# sapflux_base_v2_1.net
KiCad netlist of a schematic drawn in EAGLE
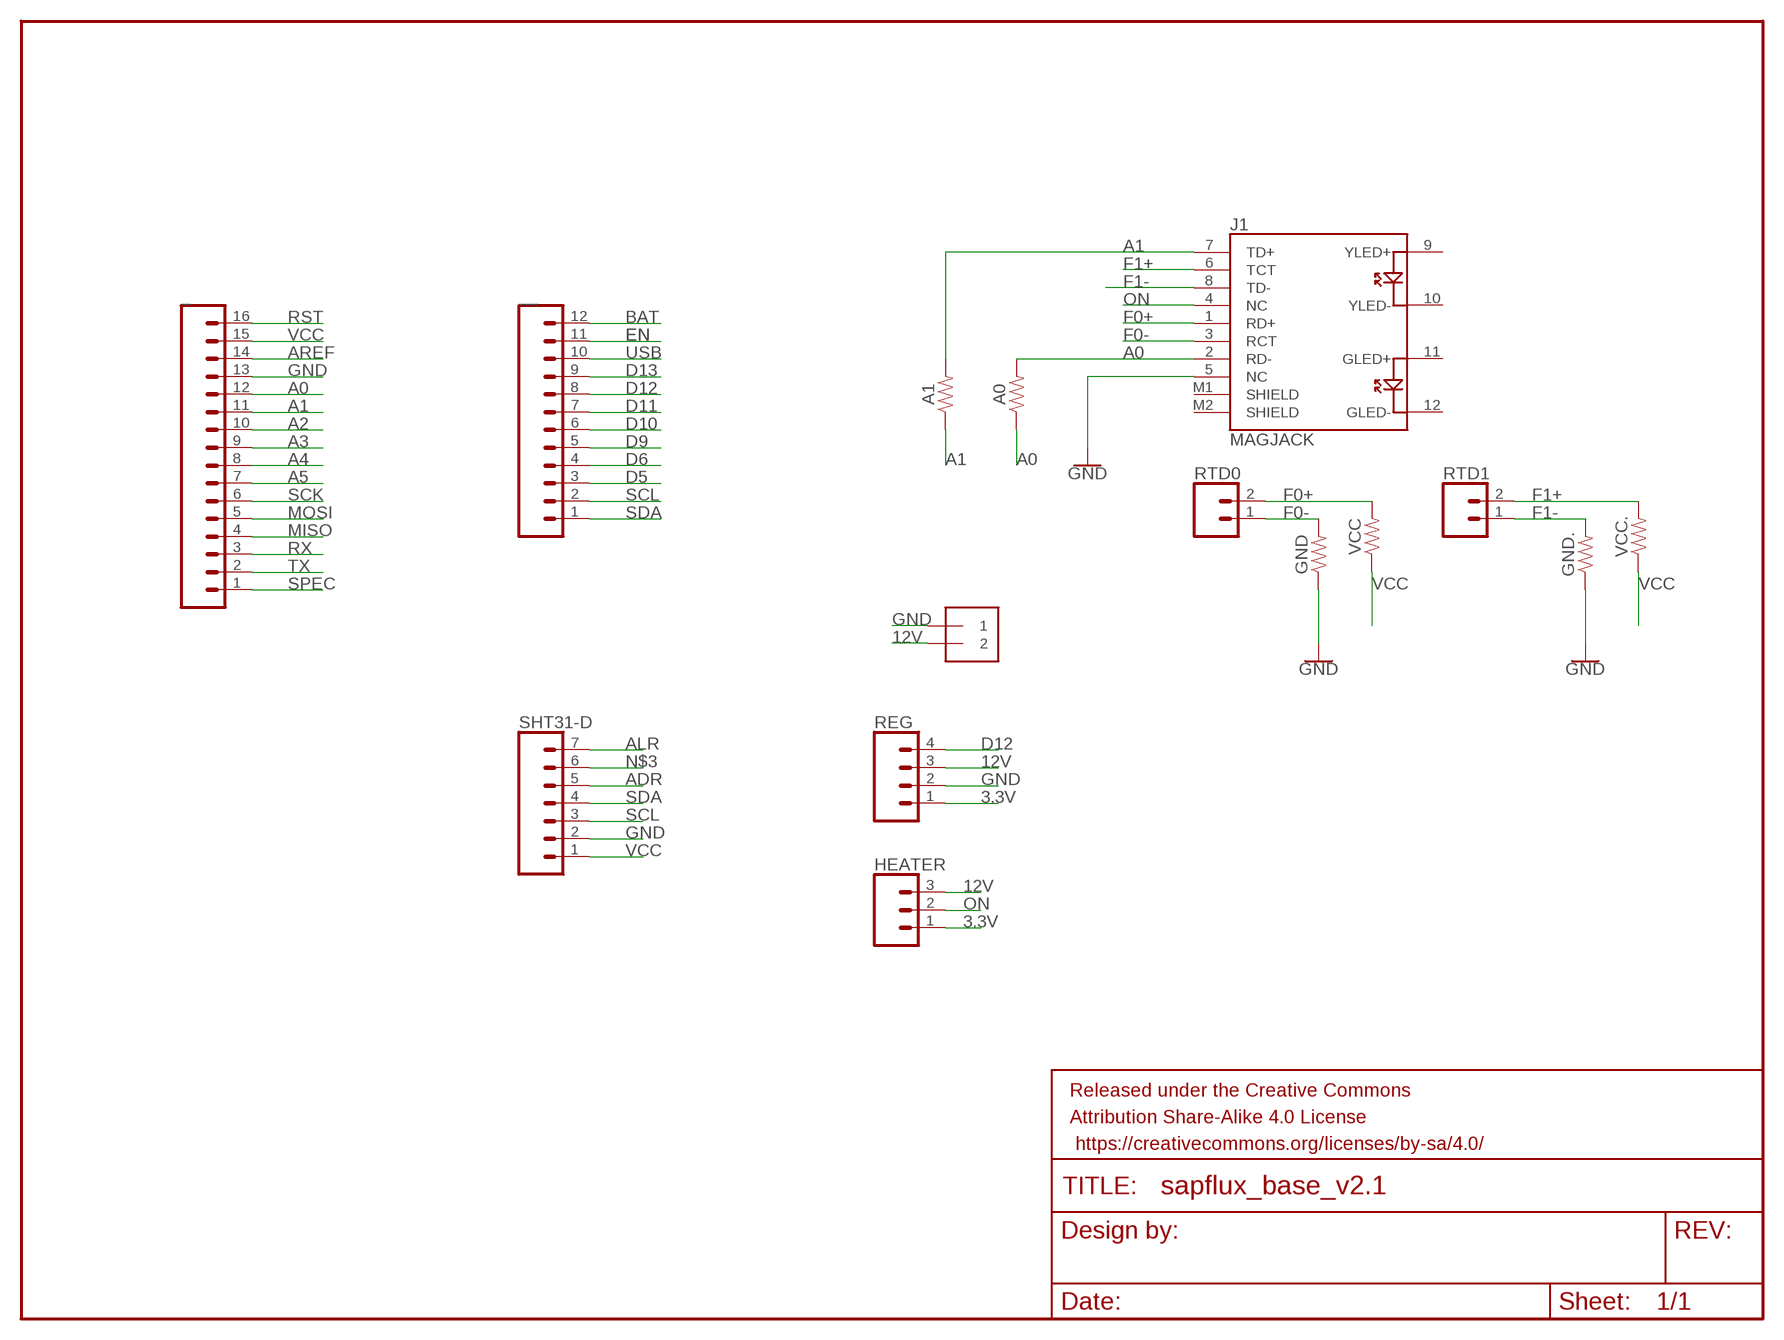
[diagram p0: schematic, sheet 1]

(export (version "E")
  (design (tool "Eeschema 10.0.6"))
  (components
    (comp (ref ".")
      (value "1X2-3.5MM")
      (footprint "eagle-import:1X2-3.5MM")
      (libsource (lib "eagle-import") (part "1X2-3.5MM"))
    )
    (comp (ref "A0")
      (value "1.8MOHM")
      (footprint "eagle-import:0603")
      (libsource (lib "eagle-import") (part "1.8MOHM"))
    )
    (comp (ref "A1")
      (value "1.8MOHM")
      (footprint "eagle-import:0603")
      (libsource (lib "eagle-import") (part "1.8MOHM"))
    )
    (comp (ref "FRAME1")
      (value "FRAME-LETTER")
      (footprint "eagle-import:CREATIVE_COMMONS")
      (libsource (lib "eagle-import") (part "FRAME-LETTER"))
    )
    (comp (ref "GND")
      (value "1.8MOHM")
      (footprint "eagle-import:0603")
      (libsource (lib "eagle-import") (part "1.8MOHM"))
    )
    (comp (ref "GND.")
      (value "1.8MOHM")
      (footprint "eagle-import:0603")
      (libsource (lib "eagle-import") (part "1.8MOHM"))
    )
    (comp (ref "HEATER")
      (value "CONN_03")
      (footprint "eagle-import:1X03")
      (libsource (lib "eagle-import") (part "CONN_03"))
    )
    (comp (ref "J1")
      (value "MAGJACK")
      (footprint "eagle-import:MAGJACK")
      (libsource (lib "eagle-import") (part "MAGJACK"))
    )
    (comp (ref "REG")
      (value "CONN_04")
      (footprint "eagle-import:1X04")
      (libsource (lib "eagle-import") (part "CONN_04"))
    )
    (comp (ref "RTD0")
      (value "CONN_02")
      (footprint "eagle-import:1X02")
      (libsource (lib "eagle-import") (part "CONN_02"))
    )
    (comp (ref "RTD1")
      (value "CONN_02")
      (footprint "eagle-import:1X02")
      (libsource (lib "eagle-import") (part "CONN_02"))
    )
    (comp (ref "SHT31-D")
      (value "CONN_07")
      (footprint "eagle-import:1X07")
      (libsource (lib "eagle-import") (part "CONN_07"))
    )
    (comp (ref "VCC")
      (value "1.8MOHM")
      (footprint "eagle-import:0603")
      (libsource (lib "eagle-import") (part "1.8MOHM"))
    )
    (comp (ref "VCC.")
      (value "1.8MOHM")
      (footprint "eagle-import:0603")
      (libsource (lib "eagle-import") (part "1.8MOHM"))
    )
    (comp (ref "_")
      (value "CONN_16")
      (footprint "eagle-import:1X16")
      (libsource (lib "eagle-import") (part "CONN_16"))
    )
    (comp (ref "__")
      (value "CONN_12")
      (footprint "eagle-import:1X12")
      (libsource (lib "eagle-import") (part "CONN_12"))
    )
  )
  (nets
    (net (code "1") (name "/3.3V") (class "Default")
      (node (ref "HEATER") (pin "1") (pinfunction "1_1") (pintype "passive"))
      (node (ref "REG") (pin "1") (pinfunction "1_1") (pintype "passive"))
    )
    (net (code "2") (name "/12V") (class "Default")
      (node (ref ".") (pin "2") (pinfunction "2_2") (pintype "passive"))
      (node (ref "HEATER") (pin "3") (pinfunction "3_3") (pintype "passive"))
      (node (ref "REG") (pin "3") (pinfunction "3_3") (pintype "passive"))
    )
    (net (code "3") (name "/A0") (class "Default")
      (node (ref "A0") (pin "1") (pinfunction "1_1") (pintype "passive"))
      (node (ref "A0") (pin "2") (pinfunction "2_2") (pintype "passive"))
      (node (ref "J1") (pin "2") (pinfunction "RD-_2") (pintype "bidirectional"))
      (node (ref "_") (pin "12") (pinfunction "12_12") (pintype "passive"))
    )
    (net (code "4") (name "/A1") (class "Default")
      (node (ref "A1") (pin "1") (pinfunction "1_1") (pintype "passive"))
      (node (ref "A1") (pin "2") (pinfunction "2_2") (pintype "passive"))
      (node (ref "J1") (pin "7") (pinfunction "TD+_7") (pintype "bidirectional"))
      (node (ref "_") (pin "11") (pinfunction "11_11") (pintype "passive"))
    )
    (net (code "5") (name "/A2") (class "Default")
      (node (ref "_") (pin "10") (pinfunction "10_10") (pintype "passive"))
    )
    (net (code "6") (name "/A3") (class "Default")
      (node (ref "_") (pin "9") (pinfunction "9_9") (pintype "passive"))
    )
    (net (code "7") (name "/A4") (class "Default")
      (node (ref "_") (pin "8") (pinfunction "8_8") (pintype "passive"))
    )
    (net (code "8") (name "/A5") (class "Default")
      (node (ref "_") (pin "7") (pinfunction "7_7") (pintype "passive"))
    )
    (net (code "9") (name "/ADR") (class "Default")
      (node (ref "SHT31-D") (pin "5") (pinfunction "5_5") (pintype "passive"))
    )
    (net (code "10") (name "/ALR") (class "Default")
      (node (ref "SHT31-D") (pin "7") (pinfunction "7_7") (pintype "passive"))
    )
    (net (code "11") (name "/AREF") (class "Default")
      (node (ref "_") (pin "14") (pinfunction "14_14") (pintype "passive"))
    )
    (net (code "12") (name "/BAT") (class "Default")
      (node (ref "__") (pin "12") (pinfunction "12_12") (pintype "passive"))
    )
    (net (code "13") (name "/D5") (class "Default")
      (node (ref "__") (pin "3") (pinfunction "3_3") (pintype "passive"))
    )
    (net (code "14") (name "/D6") (class "Default")
      (node (ref "__") (pin "4") (pinfunction "4_4") (pintype "passive"))
    )
    (net (code "15") (name "/D9") (class "Default")
      (node (ref "__") (pin "5") (pinfunction "5_5") (pintype "passive"))
    )
    (net (code "16") (name "/D10") (class "Default")
      (node (ref "__") (pin "6") (pinfunction "6_6") (pintype "passive"))
    )
    (net (code "17") (name "/D11") (class "Default")
      (node (ref "__") (pin "7") (pinfunction "7_7") (pintype "passive"))
    )
    (net (code "18") (name "/D12") (class "Default")
      (node (ref "REG") (pin "4") (pinfunction "4_4") (pintype "passive"))
      (node (ref "__") (pin "8") (pinfunction "8_8") (pintype "passive"))
    )
    (net (code "19") (name "/D13") (class "Default")
      (node (ref "__") (pin "9") (pinfunction "9_9") (pintype "passive"))
    )
    (net (code "20") (name "/EN") (class "Default")
      (node (ref "__") (pin "11") (pinfunction "11_11") (pintype "passive"))
    )
    (net (code "21") (name "/F0+") (class "Default")
      (node (ref "J1") (pin "1") (pinfunction "RD+_1") (pintype "bidirectional"))
      (node (ref "RTD0") (pin "2") (pinfunction "2_2") (pintype "passive"))
      (node (ref "VCC") (pin "2") (pinfunction "2_2") (pintype "passive"))
    )
    (net (code "22") (name "/F0-") (class "Default")
      (node (ref "GND") (pin "2") (pinfunction "2_2") (pintype "passive"))
      (node (ref "J1") (pin "3") (pinfunction "RCT_3") (pintype "bidirectional"))
      (node (ref "RTD0") (pin "1") (pinfunction "1_1") (pintype "passive"))
    )
    (net (code "23") (name "/F1+") (class "Default")
      (node (ref "J1") (pin "6") (pinfunction "TCT_6") (pintype "bidirectional"))
      (node (ref "RTD1") (pin "2") (pinfunction "2_2") (pintype "passive"))
      (node (ref "VCC.") (pin "2") (pinfunction "2_2") (pintype "passive"))
    )
    (net (code "24") (name "/F1-") (class "Default")
      (node (ref "GND.") (pin "2") (pinfunction "2_2") (pintype "passive"))
      (node (ref "J1") (pin "8") (pinfunction "TD-_8") (pintype "bidirectional"))
      (node (ref "RTD1") (pin "1") (pinfunction "1_1") (pintype "passive"))
    )
    (net (code "25") (name "/MISO") (class "Default")
      (node (ref "_") (pin "4") (pinfunction "4_4") (pintype "passive"))
    )
    (net (code "26") (name "/MOSI") (class "Default")
      (node (ref "_") (pin "5") (pinfunction "5_5") (pintype "passive"))
    )
    (net (code "27") (name "/N$3") (class "Default")
      (node (ref "SHT31-D") (pin "6") (pinfunction "6_6") (pintype "passive"))
    )
    (net (code "28") (name "/ON") (class "Default")
      (node (ref "HEATER") (pin "2") (pinfunction "2_2") (pintype "passive"))
      (node (ref "J1") (pin "4") (pinfunction "NC_4") (pintype "bidirectional"))
    )
    (net (code "29") (name "/RST") (class "Default")
      (node (ref "_") (pin "16") (pinfunction "16_16") (pintype "passive"))
    )
    (net (code "30") (name "/RX") (class "Default")
      (node (ref "_") (pin "3") (pinfunction "3_3") (pintype "passive"))
    )
    (net (code "31") (name "/SCK") (class "Default")
      (node (ref "_") (pin "6") (pinfunction "6_6") (pintype "passive"))
    )
    (net (code "32") (name "/SCL") (class "Default")
      (node (ref "SHT31-D") (pin "3") (pinfunction "3_3") (pintype "passive"))
      (node (ref "__") (pin "2") (pinfunction "2_2") (pintype "passive"))
    )
    (net (code "33") (name "/SDA") (class "Default")
      (node (ref "SHT31-D") (pin "4") (pinfunction "4_4") (pintype "passive"))
      (node (ref "__") (pin "1") (pinfunction "1_1") (pintype "passive"))
    )
    (net (code "34") (name "/SPEC") (class "Default")
      (node (ref "_") (pin "1") (pinfunction "1_1") (pintype "passive"))
    )
    (net (code "35") (name "/TX") (class "Default")
      (node (ref "_") (pin "2") (pinfunction "2_2") (pintype "passive"))
    )
    (net (code "36") (name "/USB") (class "Default")
      (node (ref "__") (pin "10") (pinfunction "10_10") (pintype "passive"))
    )
    (net (code "37") (name "/VCC") (class "Default")
      (node (ref "SHT31-D") (pin "1") (pinfunction "1_1") (pintype "passive"))
      (node (ref "VCC") (pin "1") (pinfunction "1_1") (pintype "passive"))
      (node (ref "VCC.") (pin "1") (pinfunction "1_1") (pintype "passive"))
      (node (ref "_") (pin "15") (pinfunction "15_15") (pintype "passive"))
    )
    (net (code "38") (name "GND") (class "Default")
      (node (ref ".") (pin "1") (pinfunction "1_1") (pintype "passive"))
      (node (ref "GND") (pin "1") (pinfunction "1_1") (pintype "passive"))
      (node (ref "GND.") (pin "1") (pinfunction "1_1") (pintype "passive"))
      (node (ref "J1") (pin "5") (pinfunction "NC_5") (pintype "bidirectional"))
      (node (ref "REG") (pin "2") (pinfunction "2_2") (pintype "passive"))
      (node (ref "SHT31-D") (pin "2") (pinfunction "2_2") (pintype "passive"))
      (node (ref "_") (pin "13") (pinfunction "13_13") (pintype "passive"))
    )
    (net (code "39") (name "unconnected-(J1-GLED+-Pad11)") (class "Default")
      (node (ref "J1") (pin "11") (pinfunction "GLED+_11") (pintype "bidirectional"))
    )
    (net (code "40") (name "unconnected-(J1-GLED--Pad12)") (class "Default")
      (node (ref "J1") (pin "12") (pinfunction "GLED-_12") (pintype "bidirectional"))
    )
    (net (code "41") (name "unconnected-(J1-SHIELD-PadM1)") (class "Default")
      (node (ref "J1") (pin "M1") (pinfunction "SHIELD_M1") (pintype "bidirectional"))
    )
    (net (code "42") (name "unconnected-(J1-SHIELD-PadM2)") (class "Default")
      (node (ref "J1") (pin "M2") (pinfunction "SHIELD_M2") (pintype "bidirectional"))
    )
    (net (code "43") (name "unconnected-(J1-YLED+-Pad9)") (class "Default")
      (node (ref "J1") (pin "9") (pinfunction "YLED+_9") (pintype "bidirectional"))
    )
    (net (code "44") (name "unconnected-(J1-YLED--Pad10)") (class "Default")
      (node (ref "J1") (pin "10") (pinfunction "YLED-_10") (pintype "bidirectional"))
    )
  )
)
